# Organ.net
KiCad netlist of a schematic drawn in EAGLE
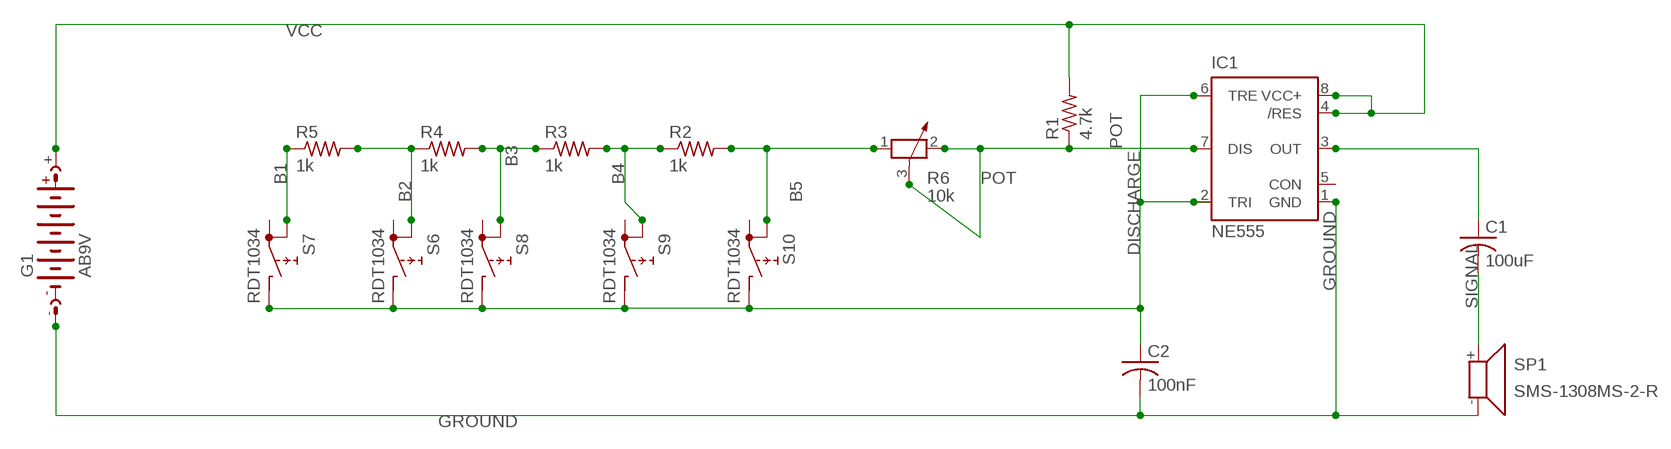
[diagram p0: schematic, sheet 1]

(export (version "E")
  (design (tool "Eeschema 10.0.6"))
  (components
    (comp (ref "C1")
      (value "100uF")
      (footprint "eagle-import:C0805")
      (libsource (lib "eagle-import") (part "C-USC0805"))
    )
    (comp (ref "C2")
      (value "100nF")
      (footprint "eagle-import:C0805")
      (libsource (lib "eagle-import") (part "C-USC0805"))
    )
    (comp (ref "G1")
      (value "AB9V")
      (footprint "eagle-import:AB9V")
      (libsource (lib "eagle-import") (part "AB9V"))
    )
    (comp (ref "IC1")
      (value "NE555")
      (footprint "eagle-import:DIL-08")
      (fields (field (name "MF") "Arrow Electronics") (field (name "MPN") "NE555N"))
      (libsource (lib "eagle-import") (part "NE555"))
    )
    (comp (ref "R1")
      (value "4.7k")
      (footprint "eagle-import:R0805")
      (libsource (lib "eagle-import") (part "R-US_R0805"))
    )
    (comp (ref "R2")
      (value "1k")
      (footprint "eagle-import:R0805")
      (libsource (lib "eagle-import") (part "R-US_R0805"))
    )
    (comp (ref "R3")
      (value "1k")
      (footprint "eagle-import:R0805")
      (libsource (lib "eagle-import") (part "R-US_R0805"))
    )
    (comp (ref "R4")
      (value "1k")
      (footprint "eagle-import:R0805")
      (libsource (lib "eagle-import") (part "R-US_R0805"))
    )
    (comp (ref "R5")
      (value "1k")
      (footprint "eagle-import:R0805")
      (libsource (lib "eagle-import") (part "R-US_R0805"))
    )
    (comp (ref "R6")
      (value "10k")
      (footprint "eagle-import:PT-10")
      (libsource (lib "eagle-import") (part "POTENTIOMETER_PT-10"))
    )
    (comp (ref "S6")
      (value "RDT1034")
      (footprint "eagle-import:RDT1034")
      (libsource (lib "eagle-import") (part "RDT1034"))
    )
    (comp (ref "S7")
      (value "RDT1034")
      (footprint "eagle-import:RDT1034")
      (libsource (lib "eagle-import") (part "RDT1034"))
    )
    (comp (ref "S8")
      (value "RDT1034")
      (footprint "eagle-import:RDT1034")
      (libsource (lib "eagle-import") (part "RDT1034"))
    )
    (comp (ref "S9")
      (value "RDT1034")
      (footprint "eagle-import:RDT1034")
      (libsource (lib "eagle-import") (part "RDT1034"))
    )
    (comp (ref "S10")
      (value "RDT1034")
      (footprint "eagle-import:RDT1034")
      (libsource (lib "eagle-import") (part "RDT1034"))
    )
    (comp (ref "SP1")
      (value "SMS-1308MS-2-R")
      (footprint "eagle-import:SMS-1308MS-2-R")
      (libsource (lib "eagle-import") (part "SMS-1308MS-2-R"))
    )
  )
  (nets
    (net (code "1") (name "/B1") (class "Default")
      (node (ref "R5") (pin "1") (pinfunction "1_1") (pintype "passive"))
      (node (ref "S7") (pin "A") (pinfunction "A_A") (pintype "passive"))
    )
    (net (code "2") (name "/B2") (class "Default")
      (node (ref "R4") (pin "1") (pinfunction "1_1") (pintype "passive"))
      (node (ref "R5") (pin "2") (pinfunction "2_2") (pintype "passive"))
      (node (ref "S6") (pin "A") (pinfunction "A_A") (pintype "passive"))
    )
    (net (code "3") (name "/B3") (class "Default")
      (node (ref "R3") (pin "1") (pinfunction "1_1") (pintype "passive"))
      (node (ref "R4") (pin "2") (pinfunction "2_2") (pintype "passive"))
      (node (ref "S8") (pin "A") (pinfunction "A_A") (pintype "passive"))
    )
    (net (code "4") (name "/B4") (class "Default")
      (node (ref "R2") (pin "1") (pinfunction "1_1") (pintype "passive"))
      (node (ref "R3") (pin "2") (pinfunction "2_2") (pintype "passive"))
      (node (ref "S9") (pin "A") (pinfunction "A_A") (pintype "passive"))
    )
    (net (code "5") (name "/B5") (class "Default")
      (node (ref "R2") (pin "2") (pinfunction "2_2") (pintype "passive"))
      (node (ref "R6") (pin "1") (pinfunction "1_1") (pintype "passive"))
      (node (ref "S10") (pin "A") (pinfunction "A_A") (pintype "passive"))
    )
    (net (code "6") (name "/DISCHARGE") (class "Default")
      (node (ref "C2") (pin "1") (pinfunction "1_1") (pintype "passive"))
      (node (ref "IC1") (pin "2") (pinfunction "TRI_2") (pintype "input"))
      (node (ref "IC1") (pin "6") (pinfunction "TRE_6") (pintype "input"))
      (node (ref "S10") (pin "B") (pinfunction "B_B") (pintype "passive"))
      (node (ref "S6") (pin "B") (pinfunction "B_B") (pintype "passive"))
      (node (ref "S7") (pin "B") (pinfunction "B_B") (pintype "passive"))
      (node (ref "S8") (pin "B") (pinfunction "B_B") (pintype "passive"))
      (node (ref "S9") (pin "B") (pinfunction "B_B") (pintype "passive"))
    )
    (net (code "7") (name "/GROUND") (class "Default")
      (node (ref "C2") (pin "2") (pinfunction "2_2") (pintype "passive"))
      (node (ref "G1") (pin "-") (pinfunction "-_-") (pintype "passive"))
      (node (ref "IC1") (pin "1") (pinfunction "GND_1") (pintype "power_in"))
      (node (ref "SP1") (pin "-") (pinfunction "2_-") (pintype "passive"))
    )
    (net (code "8") (name "/POT") (class "Default")
      (node (ref "IC1") (pin "7") (pinfunction "DIS_7") (pintype "input"))
      (node (ref "R1") (pin "1") (pinfunction "1_1") (pintype "passive"))
      (node (ref "R6") (pin "2") (pinfunction "2_2") (pintype "passive"))
      (node (ref "R6") (pin "3") (pinfunction "3_3") (pintype "passive"))
    )
    (net (code "9") (name "/SIGNAL") (class "Default")
      (node (ref "C1") (pin "2") (pinfunction "2_2") (pintype "passive"))
      (node (ref "SP1") (pin "+") (pinfunction "1_+") (pintype "passive"))
    )
    (net (code "10") (name "/VCC") (class "Default")
      (node (ref "G1") (pin "+") (pinfunction "+_+") (pintype "passive"))
      (node (ref "IC1") (pin "4") (pinfunction "/RES_4") (pintype "input"))
      (node (ref "IC1") (pin "8") (pinfunction "VCC+_8") (pintype "power_in"))
      (node (ref "R1") (pin "2") (pinfunction "2_2") (pintype "passive"))
    )
    (net (code "11") (name "Net-(IC1-OUT)") (class "Default")
      (node (ref "C1") (pin "1") (pinfunction "1_1") (pintype "passive"))
      (node (ref "IC1") (pin "3") (pinfunction "OUT_3") (pintype "output"))
    )
    (net (code "12") (name "unconnected-(IC1-CON-Pad5)") (class "Default")
      (node (ref "IC1") (pin "5") (pinfunction "CON_5") (pintype "input"))
    )
    (net (code "13") (name "unconnected-(S6-PadA1)") (class "Default")
      (node (ref "S6") (pin "A1") (pinfunction "A1_A1") (pintype "passive"))
    )
    (net (code "14") (name "unconnected-(S7-PadA1)") (class "Default")
      (node (ref "S7") (pin "A1") (pinfunction "A1_A1") (pintype "passive"))
    )
    (net (code "15") (name "unconnected-(S8-PadA1)") (class "Default")
      (node (ref "S8") (pin "A1") (pinfunction "A1_A1") (pintype "passive"))
    )
    (net (code "16") (name "unconnected-(S9-PadA1)") (class "Default")
      (node (ref "S9") (pin "A1") (pinfunction "A1_A1") (pintype "passive"))
    )
    (net (code "17") (name "unconnected-(S10-PadA1)") (class "Default")
      (node (ref "S10") (pin "A1") (pinfunction "A1_A1") (pintype "passive"))
    )
  )
)
